# AstroHub.net
KiCad netlist of a schematic drawn in EAGLE
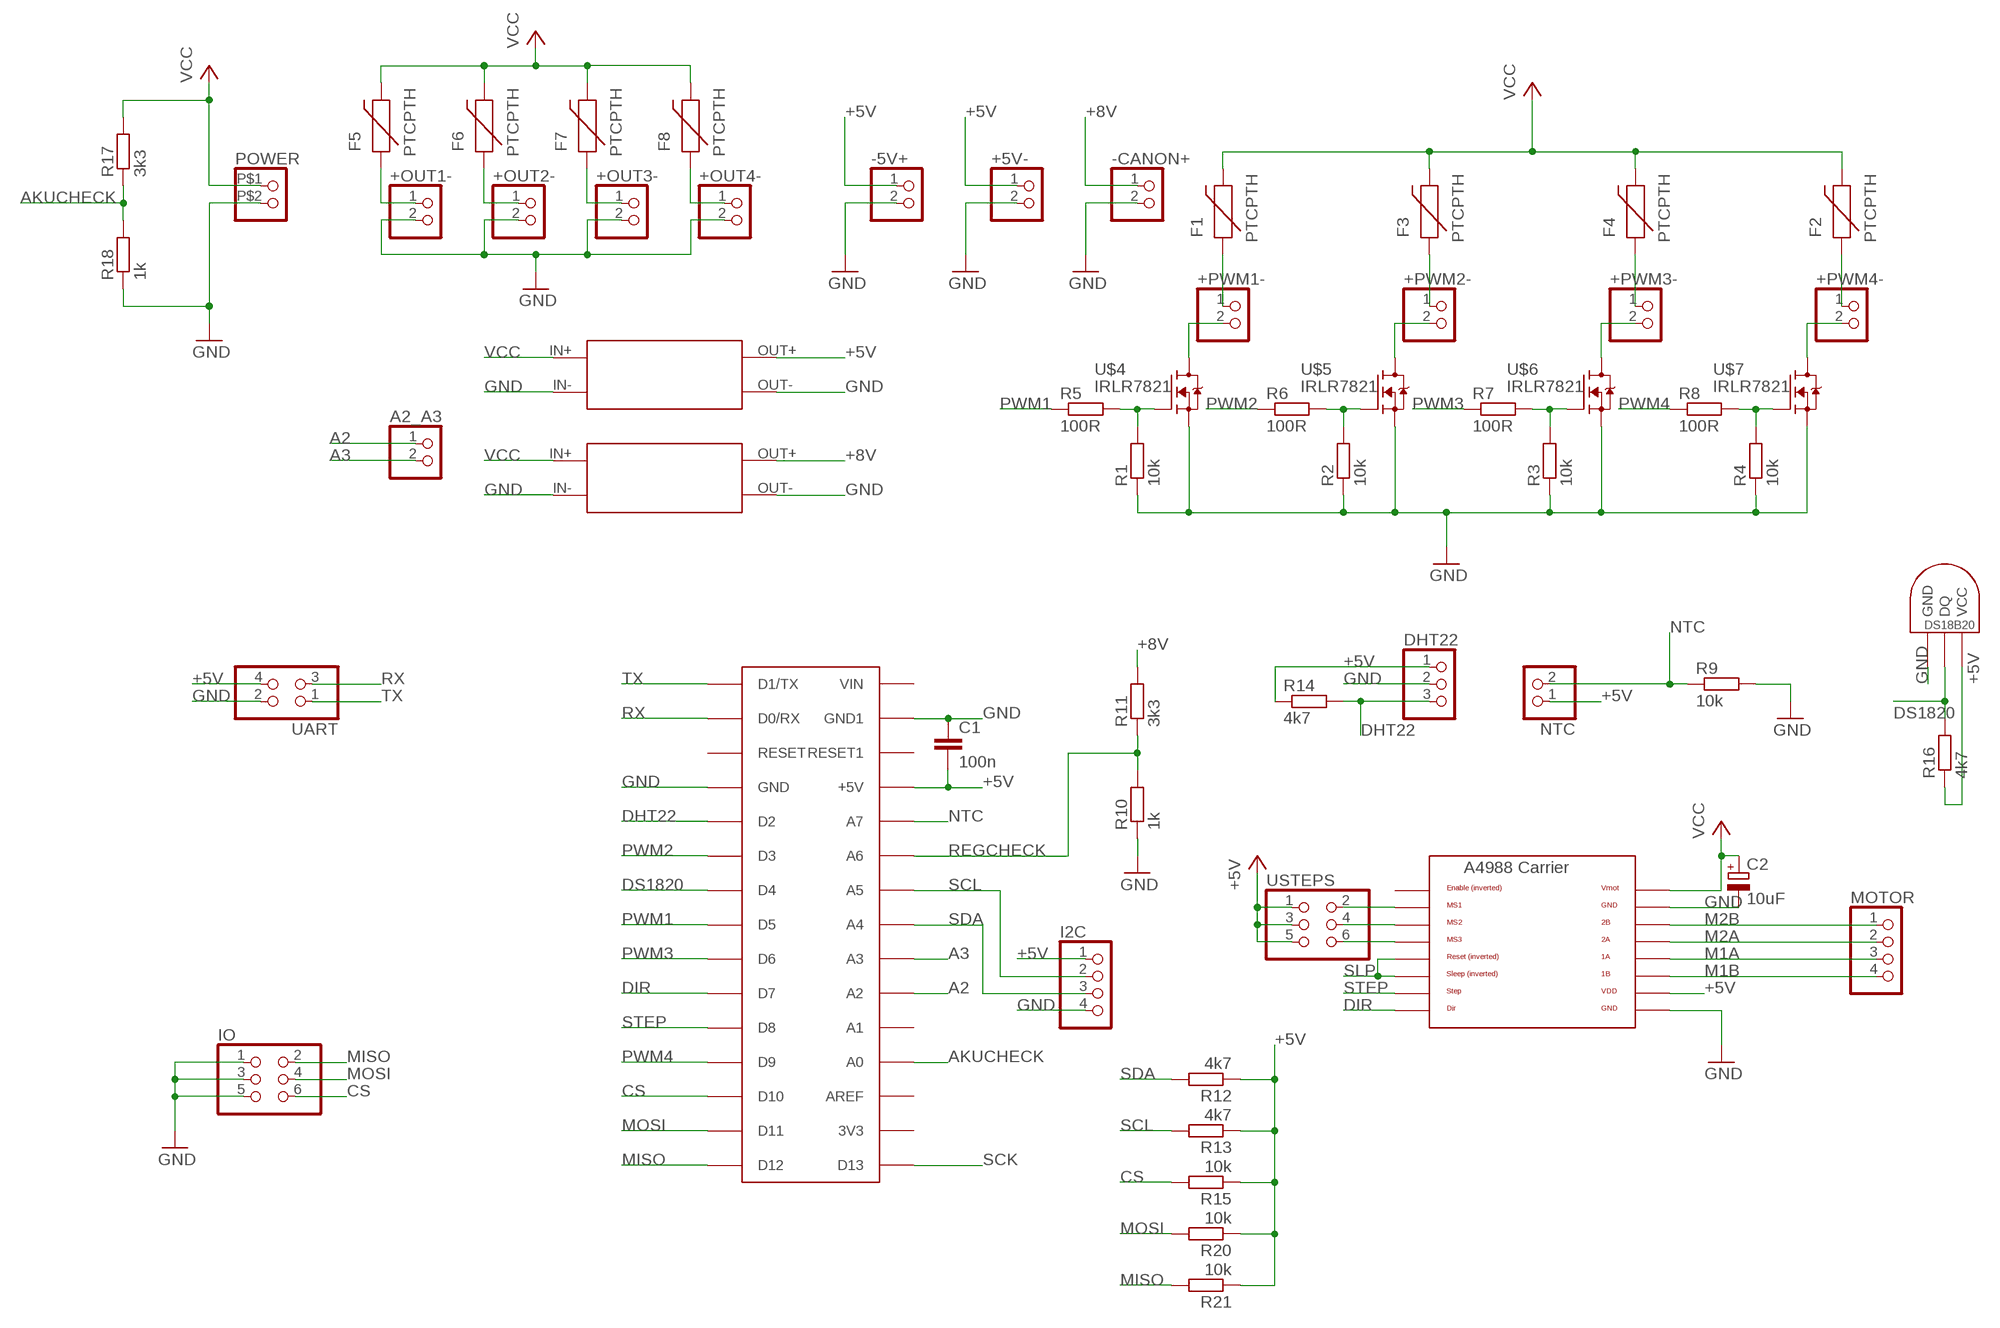
[diagram p0: schematic, sheet 1]

(export (version "E")
  (design (tool "Eeschema 10.0.6"))
  (components
    (comp (ref "+5V-")
      (value "PINHD-1X2")
      (footprint "eagle-import:1X02")
      (libsource (lib "eagle-import") (part "PINHD-1X2"))
    )
    (comp (ref "+OUT1-")
      (value "PINHD-1X2")
      (footprint "eagle-import:1X02")
      (libsource (lib "eagle-import") (part "PINHD-1X2"))
    )
    (comp (ref "+OUT2-")
      (value "PINHD-1X2")
      (footprint "eagle-import:1X02")
      (libsource (lib "eagle-import") (part "PINHD-1X2"))
    )
    (comp (ref "+OUT3-")
      (value "PINHD-1X2")
      (footprint "eagle-import:1X02")
      (libsource (lib "eagle-import") (part "PINHD-1X2"))
    )
    (comp (ref "+OUT4-")
      (value "PINHD-1X2")
      (footprint "eagle-import:1X02")
      (libsource (lib "eagle-import") (part "PINHD-1X2"))
    )
    (comp (ref "+PWM1-")
      (value "PINHD-1X2")
      (footprint "eagle-import:1X02")
      (libsource (lib "eagle-import") (part "PINHD-1X2"))
    )
    (comp (ref "+PWM2-")
      (value "PINHD-1X2")
      (footprint "eagle-import:1X02")
      (libsource (lib "eagle-import") (part "PINHD-1X2"))
    )
    (comp (ref "+PWM3-")
      (value "PINHD-1X2")
      (footprint "eagle-import:1X02")
      (libsource (lib "eagle-import") (part "PINHD-1X2"))
    )
    (comp (ref "+PWM4-")
      (value "PINHD-1X2")
      (footprint "eagle-import:1X02")
      (libsource (lib "eagle-import") (part "PINHD-1X2"))
    )
    (comp (ref "-5V+")
      (value "PINHD-1X2")
      (footprint "eagle-import:1X02")
      (libsource (lib "eagle-import") (part "PINHD-1X2"))
    )
    (comp (ref "-CANON+")
      (value "PINHD-1X2")
      (footprint "eagle-import:1X02")
      (libsource (lib "eagle-import") (part "PINHD-1X2"))
    )
    (comp (ref "A2_A3")
      (value "PINHD-1X2")
      (footprint "eagle-import:1X02")
      (libsource (lib "eagle-import") (part "PINHD-1X2"))
    )
    (comp (ref "C1")
      (value "100n")
      (footprint "eagle-import:C0603")
      (libsource (lib "eagle-import") (part "C-EUC0603"))
    )
    (comp (ref "C2")
      (value "10uF")
      (footprint "eagle-import:SMC_D")
      (libsource (lib "eagle-import") (part "CPOL-EUSMCD"))
    )
    (comp (ref "DHT22")
      (value "PINHD-1X3")
      (footprint "eagle-import:1X03")
      (libsource (lib "eagle-import") (part "PINHD-1X3"))
    )
    (comp (ref "F1")
      (value "PTCPTH")
      (footprint "eagle-import:PTC")
      (libsource (lib "eagle-import") (part "PTCPTH"))
    )
    (comp (ref "F2")
      (value "PTCPTH")
      (footprint "eagle-import:PTC")
      (libsource (lib "eagle-import") (part "PTCPTH"))
    )
    (comp (ref "F3")
      (value "PTCPTH")
      (footprint "eagle-import:PTC")
      (libsource (lib "eagle-import") (part "PTCPTH"))
    )
    (comp (ref "F4")
      (value "PTCPTH")
      (footprint "eagle-import:PTC")
      (libsource (lib "eagle-import") (part "PTCPTH"))
    )
    (comp (ref "F5")
      (value "PTCPTH")
      (footprint "eagle-import:PTC")
      (libsource (lib "eagle-import") (part "PTCPTH"))
    )
    (comp (ref "F6")
      (value "PTCPTH")
      (footprint "eagle-import:PTC")
      (libsource (lib "eagle-import") (part "PTCPTH"))
    )
    (comp (ref "F7")
      (value "PTCPTH")
      (footprint "eagle-import:PTC")
      (libsource (lib "eagle-import") (part "PTCPTH"))
    )
    (comp (ref "F8")
      (value "PTCPTH")
      (footprint "eagle-import:PTC")
      (libsource (lib "eagle-import") (part "PTCPTH"))
    )
    (comp (ref "I2C")
      (value "PINHD-1X4")
      (footprint "eagle-import:1X04")
      (libsource (lib "eagle-import") (part "PINHD-1X4"))
    )
    (comp (ref "IO")
      (value "PINHD-2X3")
      (footprint "eagle-import:2X03")
      (libsource (lib "eagle-import") (part "PINHD-2X3"))
    )
    (comp (ref "MOTOR")
      (value "PINHD-1X4")
      (footprint "eagle-import:1X04")
      (libsource (lib "eagle-import") (part "PINHD-1X4"))
    )
    (comp (ref "NTC")
      (value "PINHD-1X2")
      (footprint "eagle-import:1X02")
      (libsource (lib "eagle-import") (part "PINHD-1X2"))
    )
    (comp (ref "POWER")
      (value "PINHD-1X2BIG")
      (footprint "eagle-import:1X02BIG")
      (libsource (lib "eagle-import") (part "PINHD-1X2BIG"))
    )
    (comp (ref "R1")
      (value "10k")
      (footprint "eagle-import:R0603")
      (libsource (lib "eagle-import") (part "R-EU_R0603"))
    )
    (comp (ref "R2")
      (value "10k")
      (footprint "eagle-import:R0603")
      (libsource (lib "eagle-import") (part "R-EU_R0603"))
    )
    (comp (ref "R3")
      (value "10k")
      (footprint "eagle-import:R0603")
      (libsource (lib "eagle-import") (part "R-EU_R0603"))
    )
    (comp (ref "R4")
      (value "10k")
      (footprint "eagle-import:R0603")
      (libsource (lib "eagle-import") (part "R-EU_R0603"))
    )
    (comp (ref "R5")
      (value "100R")
      (footprint "eagle-import:R0603")
      (libsource (lib "eagle-import") (part "R-EU_R0603"))
    )
    (comp (ref "R6")
      (value "100R")
      (footprint "eagle-import:R0603")
      (libsource (lib "eagle-import") (part "R-EU_R0603"))
    )
    (comp (ref "R7")
      (value "100R")
      (footprint "eagle-import:R0603")
      (libsource (lib "eagle-import") (part "R-EU_R0603"))
    )
    (comp (ref "R8")
      (value "100R")
      (footprint "eagle-import:R0603")
      (libsource (lib "eagle-import") (part "R-EU_R0603"))
    )
    (comp (ref "R9")
      (value "10k")
      (footprint "eagle-import:R0603")
      (libsource (lib "eagle-import") (part "R-EU_R0603"))
    )
    (comp (ref "R10")
      (value "1k")
      (footprint "eagle-import:R0603")
      (libsource (lib "eagle-import") (part "R-EU_R0603"))
    )
    (comp (ref "R11")
      (value "3k3")
      (footprint "eagle-import:R0603")
      (libsource (lib "eagle-import") (part "R-EU_R0603"))
    )
    (comp (ref "R12")
      (value "4k7")
      (footprint "eagle-import:R0603")
      (libsource (lib "eagle-import") (part "R-EU_R0603"))
    )
    (comp (ref "R13")
      (value "4k7")
      (footprint "eagle-import:R0603")
      (libsource (lib "eagle-import") (part "R-EU_R0603"))
    )
    (comp (ref "R14")
      (value "4k7")
      (footprint "eagle-import:R0603")
      (libsource (lib "eagle-import") (part "R-EU_R0603"))
    )
    (comp (ref "R15")
      (value "10k")
      (footprint "eagle-import:R0603")
      (libsource (lib "eagle-import") (part "R-EU_R0603"))
    )
    (comp (ref "R16")
      (value "4k7")
      (footprint "eagle-import:R0603")
      (libsource (lib "eagle-import") (part "R-EU_R0603"))
    )
    (comp (ref "R17")
      (value "3k3")
      (footprint "eagle-import:R0603")
      (libsource (lib "eagle-import") (part "R-EU_R0603"))
    )
    (comp (ref "R18")
      (value "1k")
      (footprint "eagle-import:R0603")
      (libsource (lib "eagle-import") (part "R-EU_R0603"))
    )
    (comp (ref "R20")
      (value "10k")
      (footprint "eagle-import:R0603")
      (libsource (lib "eagle-import") (part "R-EU_R0603"))
    )
    (comp (ref "R21")
      (value "10k")
      (footprint "eagle-import:R0603")
      (libsource (lib "eagle-import") (part "R-EU_R0603"))
    )
    (comp (ref "U$1")
      (value "ARDUINONANO")
      (footprint "eagle-import:PDIP-32")
      (libsource (lib "eagle-import") (part "ARDUINONANO"))
    )
    (comp (ref "U$2")
      (value "LM2596BOARD")
      (footprint "eagle-import:LM2596BOARD")
      (libsource (lib "eagle-import") (part "LM2596BOARD"))
    )
    (comp (ref "U$3")
      (value "A4988BREAKOUT")
      (footprint "eagle-import:A4988BREAKOUT")
      (libsource (lib "eagle-import") (part "A4988BREAKOUT"))
    )
    (comp (ref "U$4")
      (value "IRLR7821")
      (footprint "eagle-import:TO252")
      (libsource (lib "eagle-import") (part "IRLR7821"))
    )
    (comp (ref "U$5")
      (value "IRLR7821")
      (footprint "eagle-import:TO252")
      (libsource (lib "eagle-import") (part "IRLR7821"))
    )
    (comp (ref "U$6")
      (value "IRLR7821")
      (footprint "eagle-import:TO252")
      (libsource (lib "eagle-import") (part "IRLR7821"))
    )
    (comp (ref "U$7")
      (value "IRLR7821")
      (footprint "eagle-import:TO252")
      (libsource (lib "eagle-import") (part "IRLR7821"))
    )
    (comp (ref "U$8")
      (value "LM2596BOARD")
      (footprint "eagle-import:LM2596BOARD")
      (libsource (lib "eagle-import") (part "LM2596BOARD"))
    )
    (comp (ref "U$9")
      (value "DS1820TO92")
      (footprint "eagle-import:DS1820")
      (libsource (lib "eagle-import") (part "DS1820TO92"))
    )
    (comp (ref "UART")
      (value "PINHD-2X2")
      (footprint "eagle-import:2X02")
      (libsource (lib "eagle-import") (part "PINHD-2X2"))
    )
    (comp (ref "USTEPS")
      (value "PINHD-2X3")
      (footprint "eagle-import:2X03")
      (libsource (lib "eagle-import") (part "PINHD-2X3"))
    )
  )
  (nets
    (net (code "1") (name "+5V") (class "Default")
      (node (ref "+5V-") (pin "1") (pinfunction "1_1") (pintype "passive"))
      (node (ref "-5V+") (pin "1") (pinfunction "1_1") (pintype "passive"))
      (node (ref "C1") (pin "2") (pinfunction "2_2") (pintype "passive"))
      (node (ref "DHT22") (pin "1") (pinfunction "1_1") (pintype "passive"))
      (node (ref "I2C") (pin "1") (pinfunction "1_1") (pintype "passive"))
      (node (ref "NTC") (pin "1") (pinfunction "1_1") (pintype "passive"))
      (node (ref "R12") (pin "1") (pinfunction "1_1") (pintype "passive"))
      (node (ref "R13") (pin "1") (pinfunction "1_1") (pintype "passive"))
      (node (ref "R14") (pin "1") (pinfunction "1_1") (pintype "passive"))
      (node (ref "R15") (pin "1") (pinfunction "1_1") (pintype "passive"))
      (node (ref "R16") (pin "1") (pinfunction "1_1") (pintype "passive"))
      (node (ref "R20") (pin "1") (pinfunction "1_1") (pintype "passive"))
      (node (ref "R21") (pin "1") (pinfunction "1_1") (pintype "passive"))
      (node (ref "U$1") (pin "+5V") (pinfunction "+5V_+5V") (pintype "bidirectional"))
      (node (ref "U$2") (pin "OUT+") (pinfunction "OUT+_OUT+") (pintype "bidirectional"))
      (node (ref "U$3") (pin "VDD") (pinfunction "VDD_VDD") (pintype "power_in"))
      (node (ref "U$9") (pin "VDD") (pinfunction "VCC_VDD") (pintype "power_in"))
      (node (ref "UART") (pin "4") (pinfunction "4_4") (pintype "passive"))
      (node (ref "USTEPS") (pin "1") (pinfunction "1_1") (pintype "passive"))
      (node (ref "USTEPS") (pin "3") (pinfunction "3_3") (pintype "passive"))
      (node (ref "USTEPS") (pin "5") (pinfunction "5_5") (pintype "passive"))
    )
    (net (code "2") (name "/+8V") (class "Default")
      (node (ref "-CANON+") (pin "1") (pinfunction "1_1") (pintype "passive"))
      (node (ref "R11") (pin "2") (pinfunction "2_2") (pintype "passive"))
      (node (ref "U$8") (pin "OUT+") (pinfunction "OUT+_OUT+") (pintype "bidirectional"))
    )
    (net (code "3") (name "/A2") (class "Default")
      (node (ref "A2_A3") (pin "1") (pinfunction "1_1") (pintype "passive"))
      (node (ref "U$1") (pin "A2") (pinfunction "A2_A2") (pintype "bidirectional"))
    )
    (net (code "4") (name "/A3") (class "Default")
      (node (ref "A2_A3") (pin "2") (pinfunction "2_2") (pintype "passive"))
      (node (ref "U$1") (pin "A3") (pinfunction "A3_A3") (pintype "bidirectional"))
    )
    (net (code "5") (name "/AKUCHECK") (class "Default")
      (node (ref "R17") (pin "1") (pinfunction "1_1") (pintype "passive"))
      (node (ref "R18") (pin "2") (pinfunction "2_2") (pintype "passive"))
      (node (ref "U$1") (pin "A0") (pinfunction "A0_A0") (pintype "bidirectional"))
    )
    (net (code "6") (name "/CS") (class "Default")
      (node (ref "IO") (pin "6") (pinfunction "6_6") (pintype "passive"))
      (node (ref "R15") (pin "2") (pinfunction "2_2") (pintype "passive"))
      (node (ref "U$1") (pin "D10") (pinfunction "D10_D10") (pintype "bidirectional"))
    )
    (net (code "7") (name "/DHT22") (class "Default")
      (node (ref "DHT22") (pin "3") (pinfunction "3_3") (pintype "passive"))
      (node (ref "R14") (pin "2") (pinfunction "2_2") (pintype "passive"))
      (node (ref "U$1") (pin "D2") (pinfunction "D2_D2") (pintype "bidirectional"))
    )
    (net (code "8") (name "/DIR") (class "Default")
      (node (ref "U$1") (pin "D7") (pinfunction "D7_D7") (pintype "bidirectional"))
      (node (ref "U$3") (pin "DIR") (pinfunction "DIR_DIR") (pintype "input"))
    )
    (net (code "9") (name "/DS1820") (class "Default")
      (node (ref "R16") (pin "2") (pinfunction "2_2") (pintype "passive"))
      (node (ref "U$1") (pin "D4") (pinfunction "D4_D4") (pintype "bidirectional"))
      (node (ref "U$9") (pin "DQ") (pinfunction "DQ_DQ") (pintype "bidirectional"))
    )
    (net (code "10") (name "/M1A") (class "Default")
      (node (ref "MOTOR") (pin "3") (pinfunction "3_3") (pintype "passive"))
      (node (ref "U$3") (pin "1A") (pinfunction "1A_1A") (pintype "output"))
    )
    (net (code "11") (name "/M1B") (class "Default")
      (node (ref "MOTOR") (pin "4") (pinfunction "4_4") (pintype "passive"))
      (node (ref "U$3") (pin "1B") (pinfunction "1B_1B") (pintype "output"))
    )
    (net (code "12") (name "/M2A") (class "Default")
      (node (ref "MOTOR") (pin "2") (pinfunction "2_2") (pintype "passive"))
      (node (ref "U$3") (pin "2A") (pinfunction "2A_2A") (pintype "output"))
    )
    (net (code "13") (name "/M2B") (class "Default")
      (node (ref "MOTOR") (pin "1") (pinfunction "1_1") (pintype "passive"))
      (node (ref "U$3") (pin "2B") (pinfunction "2B_2B") (pintype "output"))
    )
    (net (code "14") (name "/MISO") (class "Default")
      (node (ref "IO") (pin "2") (pinfunction "2_2") (pintype "passive"))
      (node (ref "R21") (pin "2") (pinfunction "2_2") (pintype "passive"))
      (node (ref "U$1") (pin "D12") (pinfunction "D12_D12") (pintype "bidirectional"))
    )
    (net (code "15") (name "/MOSI") (class "Default")
      (node (ref "IO") (pin "4") (pinfunction "4_4") (pintype "passive"))
      (node (ref "R20") (pin "2") (pinfunction "2_2") (pintype "passive"))
      (node (ref "U$1") (pin "D11") (pinfunction "D11_D11") (pintype "bidirectional"))
    )
    (net (code "16") (name "/NTC") (class "Default")
      (node (ref "NTC") (pin "2") (pinfunction "2_2") (pintype "passive"))
      (node (ref "R9") (pin "1") (pinfunction "1_1") (pintype "passive"))
      (node (ref "U$1") (pin "A7") (pinfunction "A7_A7") (pintype "bidirectional"))
    )
    (net (code "17") (name "/PWM1") (class "Default")
      (node (ref "R5") (pin "1") (pinfunction "1_1") (pintype "passive"))
      (node (ref "U$1") (pin "D5") (pinfunction "D5_D5") (pintype "bidirectional"))
    )
    (net (code "18") (name "/PWM2") (class "Default")
      (node (ref "R6") (pin "1") (pinfunction "1_1") (pintype "passive"))
      (node (ref "U$1") (pin "D3") (pinfunction "D3_D3") (pintype "bidirectional"))
    )
    (net (code "19") (name "/PWM3") (class "Default")
      (node (ref "R7") (pin "1") (pinfunction "1_1") (pintype "passive"))
      (node (ref "U$1") (pin "D6") (pinfunction "D6_D6") (pintype "bidirectional"))
    )
    (net (code "20") (name "/PWM4") (class "Default")
      (node (ref "R8") (pin "1") (pinfunction "1_1") (pintype "passive"))
      (node (ref "U$1") (pin "D9") (pinfunction "D9_D9") (pintype "bidirectional"))
    )
    (net (code "21") (name "/REGCHECK") (class "Default")
      (node (ref "R10") (pin "2") (pinfunction "2_2") (pintype "passive"))
      (node (ref "R11") (pin "1") (pinfunction "1_1") (pintype "passive"))
      (node (ref "U$1") (pin "A6") (pinfunction "A6_A6") (pintype "bidirectional"))
    )
    (net (code "22") (name "/RX") (class "Default")
      (node (ref "U$1") (pin "D0/RX") (pinfunction "D0/RX_D0/RX") (pintype "bidirectional"))
      (node (ref "UART") (pin "3") (pinfunction "3_3") (pintype "passive"))
    )
    (net (code "23") (name "/SCK") (class "Default")
      (node (ref "U$1") (pin "D13") (pinfunction "D13_D13") (pintype "bidirectional"))
    )
    (net (code "24") (name "/SCL") (class "Default")
      (node (ref "I2C") (pin "2") (pinfunction "2_2") (pintype "passive"))
      (node (ref "R13") (pin "2") (pinfunction "2_2") (pintype "passive"))
      (node (ref "U$1") (pin "A5") (pinfunction "A5_A5") (pintype "bidirectional"))
    )
    (net (code "25") (name "/SDA") (class "Default")
      (node (ref "I2C") (pin "3") (pinfunction "3_3") (pintype "passive"))
      (node (ref "R12") (pin "2") (pinfunction "2_2") (pintype "passive"))
      (node (ref "U$1") (pin "A4") (pinfunction "A4_A4") (pintype "bidirectional"))
    )
    (net (code "26") (name "/SLP") (class "Default")
      (node (ref "U$3") (pin "RST") (pinfunction "RST_RST") (pintype "input"))
      (node (ref "U$3") (pin "SLP") (pinfunction "SLEEP_SLP") (pintype "input"))
    )
    (net (code "27") (name "/STEP") (class "Default")
      (node (ref "U$1") (pin "D8") (pinfunction "D8_D8") (pintype "bidirectional"))
      (node (ref "U$3") (pin "STEP") (pinfunction "STEP_STEP") (pintype "input"))
    )
    (net (code "28") (name "/TX") (class "Default")
      (node (ref "U$1") (pin "D1/TX") (pinfunction "D1/TX_D1/TX") (pintype "bidirectional"))
      (node (ref "UART") (pin "1") (pinfunction "1_1") (pintype "passive"))
    )
    (net (code "29") (name "GND") (class "Default")
      (node (ref "+5V-") (pin "2") (pinfunction "2_2") (pintype "passive"))
      (node (ref "+OUT1-") (pin "2") (pinfunction "2_2") (pintype "passive"))
      (node (ref "+OUT2-") (pin "2") (pinfunction "2_2") (pintype "passive"))
      (node (ref "+OUT3-") (pin "2") (pinfunction "2_2") (pintype "passive"))
      (node (ref "+OUT4-") (pin "2") (pinfunction "2_2") (pintype "passive"))
      (node (ref "-5V+") (pin "2") (pinfunction "2_2") (pintype "passive"))
      (node (ref "-CANON+") (pin "2") (pinfunction "2_2") (pintype "passive"))
      (node (ref "C1") (pin "1") (pinfunction "1_1") (pintype "passive"))
      (node (ref "C2") (pin "-") (pinfunction "-_-") (pintype "passive"))
      (node (ref "DHT22") (pin "2") (pinfunction "2_2") (pintype "passive"))
      (node (ref "I2C") (pin "4") (pinfunction "4_4") (pintype "passive"))
      (node (ref "IO") (pin "1") (pinfunction "1_1") (pintype "passive"))
      (node (ref "IO") (pin "3") (pinfunction "3_3") (pintype "passive"))
      (node (ref "IO") (pin "5") (pinfunction "5_5") (pintype "passive"))
      (node (ref "POWER") (pin "P$2") (pinfunction "2_P$2") (pintype "passive"))
      (node (ref "R1") (pin "1") (pinfunction "1_1") (pintype "passive"))
      (node (ref "R10") (pin "1") (pinfunction "1_1") (pintype "passive"))
      (node (ref "R18") (pin "1") (pinfunction "1_1") (pintype "passive"))
      (node (ref "R2") (pin "1") (pinfunction "1_1") (pintype "passive"))
      (node (ref "R3") (pin "1") (pinfunction "1_1") (pintype "passive"))
      (node (ref "R4") (pin "1") (pinfunction "1_1") (pintype "passive"))
      (node (ref "R9") (pin "2") (pinfunction "2_2") (pintype "passive"))
      (node (ref "U$1") (pin "GND") (pinfunction "GND_GND") (pintype "bidirectional"))
      (node (ref "U$1") (pin "GND1") (pinfunction "GND1_GND1") (pintype "bidirectional"))
      (node (ref "U$2") (pin "IN-") (pinfunction "IN-_IN-") (pintype "bidirectional"))
      (node (ref "U$2") (pin "OUT-") (pinfunction "OUT-_OUT-") (pintype "bidirectional"))
      (node (ref "U$3") (pin "GND") (pinfunction "GND_GND") (pintype "power_in"))
      (node (ref "U$3") (pin "GND@0") (pinfunction "GND_GND@0") (pintype "power_in"))
      (node (ref "U$4") (pin "2") (pinfunction "S_2") (pintype "passive"))
      (node (ref "U$5") (pin "2") (pinfunction "S_2") (pintype "passive"))
      (node (ref "U$6") (pin "2") (pinfunction "S_2") (pintype "passive"))
      (node (ref "U$7") (pin "2") (pinfunction "S_2") (pintype "passive"))
      (node (ref "U$8") (pin "IN-") (pinfunction "IN-_IN-") (pintype "bidirectional"))
      (node (ref "U$8") (pin "OUT-") (pinfunction "OUT-_OUT-") (pintype "bidirectional"))
      (node (ref "U$9") (pin "GND") (pinfunction "GND_GND") (pintype "power_in"))
      (node (ref "UART") (pin "2") (pinfunction "2_2") (pintype "passive"))
    )
    (net (code "30") (name "Net-(F1-1)") (class "Default")
      (node (ref "+PWM1-") (pin "1") (pinfunction "1_1") (pintype "passive"))
      (node (ref "F1") (pin "P$1") (pinfunction "1_P$1") (pintype "bidirectional"))
    )
    (net (code "31") (name "Net-(F2-1)") (class "Default")
      (node (ref "+PWM4-") (pin "1") (pinfunction "1_1") (pintype "passive"))
      (node (ref "F2") (pin "P$1") (pinfunction "1_P$1") (pintype "bidirectional"))
    )
    (net (code "32") (name "Net-(F3-1)") (class "Default")
      (node (ref "+PWM2-") (pin "1") (pinfunction "1_1") (pintype "passive"))
      (node (ref "F3") (pin "P$1") (pinfunction "1_P$1") (pintype "bidirectional"))
    )
    (net (code "33") (name "Net-(F4-1)") (class "Default")
      (node (ref "+PWM3-") (pin "1") (pinfunction "1_1") (pintype "passive"))
      (node (ref "F4") (pin "P$1") (pinfunction "1_P$1") (pintype "bidirectional"))
    )
    (net (code "34") (name "Net-(F5-1)") (class "Default")
      (node (ref "+OUT1-") (pin "1") (pinfunction "1_1") (pintype "passive"))
      (node (ref "F5") (pin "P$1") (pinfunction "1_P$1") (pintype "bidirectional"))
    )
    (net (code "35") (name "Net-(F6-1)") (class "Default")
      (node (ref "+OUT2-") (pin "1") (pinfunction "1_1") (pintype "passive"))
      (node (ref "F6") (pin "P$1") (pinfunction "1_P$1") (pintype "bidirectional"))
    )
    (net (code "36") (name "Net-(F7-1)") (class "Default")
      (node (ref "+OUT3-") (pin "1") (pinfunction "1_1") (pintype "passive"))
      (node (ref "F7") (pin "P$1") (pinfunction "1_P$1") (pintype "bidirectional"))
    )
    (net (code "37") (name "Net-(F8-1)") (class "Default")
      (node (ref "+OUT4-") (pin "1") (pinfunction "1_1") (pintype "passive"))
      (node (ref "F8") (pin "P$1") (pinfunction "1_P$1") (pintype "bidirectional"))
    )
    (net (code "38") (name "Net-(U$3-PadMS1)") (class "Default")
      (node (ref "U$3") (pin "MS1") (pinfunction "MS1_MS1") (pintype "input"))
      (node (ref "USTEPS") (pin "2") (pinfunction "2_2") (pintype "passive"))
    )
    (net (code "39") (name "Net-(U$3-PadMS2)") (class "Default")
      (node (ref "U$3") (pin "MS2") (pinfunction "MS2_MS2") (pintype "input"))
      (node (ref "USTEPS") (pin "4") (pinfunction "4_4") (pintype "passive"))
    )
    (net (code "40") (name "Net-(U$3-PadMS3)") (class "Default")
      (node (ref "U$3") (pin "MS3") (pinfunction "MS3_MS3") (pintype "input"))
      (node (ref "USTEPS") (pin "6") (pinfunction "6_6") (pintype "passive"))
    )
    (net (code "41") (name "Net-(U$4-D)") (class "Default")
      (node (ref "+PWM1-") (pin "2") (pinfunction "2_2") (pintype "passive"))
      (node (ref "U$4") (pin "3") (pinfunction "D_3") (pintype "passive"))
    )
    (net (code "42") (name "Net-(U$4-G)") (class "Default")
      (node (ref "R1") (pin "2") (pinfunction "2_2") (pintype "passive"))
      (node (ref "R5") (pin "2") (pinfunction "2_2") (pintype "passive"))
      (node (ref "U$4") (pin "1") (pinfunction "G_1") (pintype "passive"))
    )
    (net (code "43") (name "Net-(U$5-D)") (class "Default")
      (node (ref "+PWM2-") (pin "2") (pinfunction "2_2") (pintype "passive"))
      (node (ref "U$5") (pin "3") (pinfunction "D_3") (pintype "passive"))
    )
    (net (code "44") (name "Net-(U$5-G)") (class "Default")
      (node (ref "R2") (pin "2") (pinfunction "2_2") (pintype "passive"))
      (node (ref "R6") (pin "2") (pinfunction "2_2") (pintype "passive"))
      (node (ref "U$5") (pin "1") (pinfunction "G_1") (pintype "passive"))
    )
    (net (code "45") (name "Net-(U$6-D)") (class "Default")
      (node (ref "+PWM3-") (pin "2") (pinfunction "2_2") (pintype "passive"))
      (node (ref "U$6") (pin "3") (pinfunction "D_3") (pintype "passive"))
    )
    (net (code "46") (name "Net-(U$6-G)") (class "Default")
      (node (ref "R3") (pin "2") (pinfunction "2_2") (pintype "passive"))
      (node (ref "R7") (pin "2") (pinfunction "2_2") (pintype "passive"))
      (node (ref "U$6") (pin "1") (pinfunction "G_1") (pintype "passive"))
    )
    (net (code "47") (name "Net-(U$7-D)") (class "Default")
      (node (ref "+PWM4-") (pin "2") (pinfunction "2_2") (pintype "passive"))
      (node (ref "U$7") (pin "3") (pinfunction "D_3") (pintype "passive"))
    )
    (net (code "48") (name "Net-(U$7-G)") (class "Default")
      (node (ref "R4") (pin "2") (pinfunction "2_2") (pintype "passive"))
      (node (ref "R8") (pin "2") (pinfunction "2_2") (pintype "passive"))
      (node (ref "U$7") (pin "1") (pinfunction "G_1") (pintype "passive"))
    )
    (net (code "49") (name "VCC") (class "Default")
      (node (ref "C2") (pin "+") (pinfunction "+_+") (pintype "passive"))
      (node (ref "F1") (pin "P$2") (pinfunction "2_P$2") (pintype "bidirectional"))
      (node (ref "F2") (pin "P$2") (pinfunction "2_P$2") (pintype "bidirectional"))
      (node (ref "F3") (pin "P$2") (pinfunction "2_P$2") (pintype "bidirectional"))
      (node (ref "F4") (pin "P$2") (pinfunction "2_P$2") (pintype "bidirectional"))
      (node (ref "F5") (pin "P$2") (pinfunction "2_P$2") (pintype "bidirectional"))
      (node (ref "F6") (pin "P$2") (pinfunction "2_P$2") (pintype "bidirectional"))
      (node (ref "F7") (pin "P$2") (pinfunction "2_P$2") (pintype "bidirectional"))
      (node (ref "F8") (pin "P$2") (pinfunction "2_P$2") (pintype "bidirectional"))
      (node (ref "POWER") (pin "P$1") (pinfunction "1_P$1") (pintype "passive"))
      (node (ref "R17") (pin "2") (pinfunction "2_2") (pintype "passive"))
      (node (ref "U$2") (pin "IN+") (pinfunction "IN+_IN+") (pintype "bidirectional"))
      (node (ref "U$3") (pin "VMOT") (pinfunction "VMOT_VMOT") (pintype "power_in"))
      (node (ref "U$8") (pin "IN+") (pinfunction "IN+_IN+") (pintype "bidirectional"))
    )
    (net (code "50") (name "unconnected-(U$1-Pad3V3)") (class "Default")
      (node (ref "U$1") (pin "3V3") (pinfunction "3V3_3V3") (pintype "bidirectional"))
    )
    (net (code "51") (name "unconnected-(U$1-PadA1)") (class "Default")
      (node (ref "U$1") (pin "A1") (pinfunction "A1_A1") (pintype "bidirectional"))
    )
    (net (code "52") (name "unconnected-(U$1-PadAREF)") (class "Default")
      (node (ref "U$1") (pin "AREF") (pinfunction "AREF_AREF") (pintype "bidirectional"))
    )
    (net (code "53") (name "unconnected-(U$1-PadRESET)") (class "Default")
      (node (ref "U$1") (pin "RESET") (pinfunction "RESET_RESET") (pintype "bidirectional"))
    )
    (net (code "54") (name "unconnected-(U$1-PadRESET1)") (class "Default")
      (node (ref "U$1") (pin "RESET1") (pinfunction "RESET1_RESET1") (pintype "bidirectional"))
    )
    (net (code "55") (name "unconnected-(U$1-PadVIN)") (class "Default")
      (node (ref "U$1") (pin "VIN") (pinfunction "VIN_VIN") (pintype "bidirectional"))
    )
    (net (code "56") (name "unconnected-(U$3-PadEN)") (class "Default")
      (node (ref "U$3") (pin "EN") (pinfunction "EN_EN") (pintype "input"))
    )
  )
)
